# Snippet_LM1117MP-5_0.net
KiCad netlist of a schematic drawn in Altium Designer
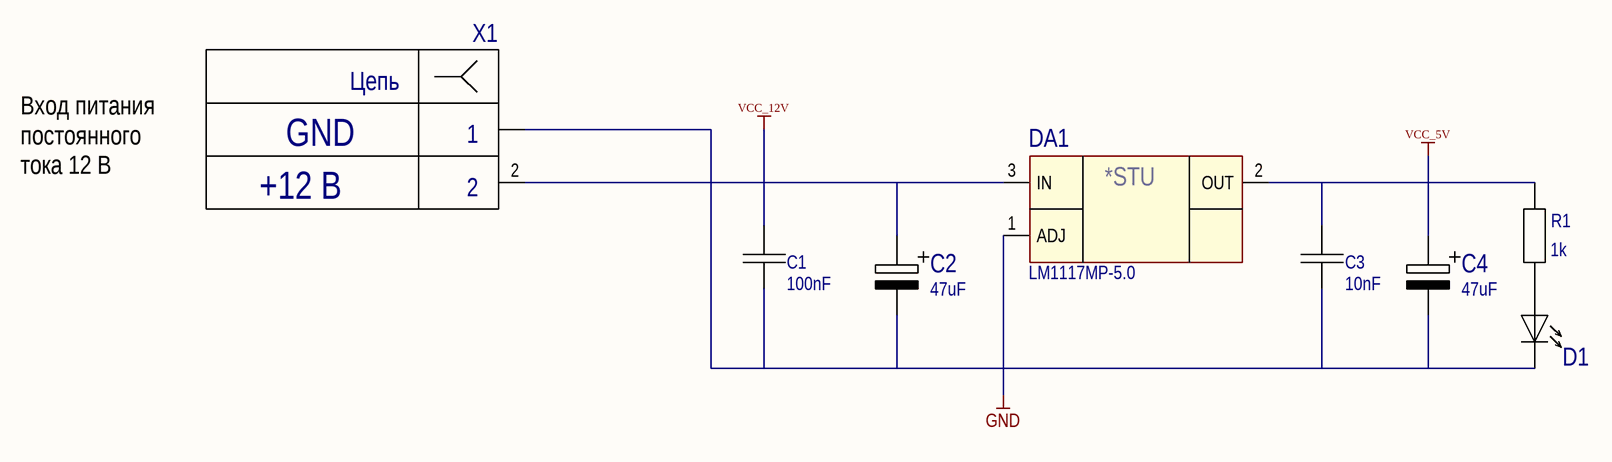
[diagram p0: Snippet_LM1117MP-5.0.SchDoc]

(export (version "E")
  (design (tool "Eeschema 10.0.6"))
  (components
    (comp (ref "C1")
      (value "100nF")
      (footprint "Capacitor_0805")
      (libsource (lib "Библиотека элементов") (part "Capacitor_0805"))
    )
    (comp (ref "C2")
      (value "47uF")
      (footprint "Capacitor_Electrolit_6.3x11")
      (libsource (lib "Библиотека элементов") (part "Capacitor+_6.3x11"))
    )
    (comp (ref "C3")
      (value "10nF")
      (footprint "Capacitor_0805")
      (libsource (lib "Библиотека элементов") (part "Capacitor_0805"))
    )
    (comp (ref "C4")
      (value "47uF")
      (footprint "CAPACITOR+_22uFx25V")
      (libsource (lib "Библиотека элементов") (part "Capacitor+_22uFx25V"))
    )
    (comp (ref "D1")
      (value "LED_2.54mm_R")
      (footprint "LED_2.54mm_R")
      (libsource (lib "Библиотека элементов") (part "LED_2.54mm_R"))
    )
    (comp (ref "DA1")
      (value "LM1117MP-5.0")
      (footprint "NCP1117_SOT223")
      (libsource (lib "Библиотека элементов") (part "LM1117MP-5.0"))
    )
    (comp (ref "R1")
      (value "1k")
      (footprint "RESISTOR_SMD0805")
      (libsource (lib "Библиотека элементов") (part "Resistor_0805"))
    )
    (comp (ref "X1")
      (value "Connector_DG350-3.5-02P-14")
      (footprint "CONNECTOR_DG350-3.5-02P-14")
      (libsource (lib "Библиотека элементов") (part "Connector_DG350-3.5-02P-14"))
    )
  )
  (nets
    (net (code "1") (name "GND") (class "Default")
      (node (ref "C1") (pin "2") (pinfunction "2_2") (pintype "passive"))
      (node (ref "C2") (pin "2") (pinfunction "2_2") (pintype "passive"))
      (node (ref "C3") (pin "2") (pinfunction "2_2") (pintype "passive"))
      (node (ref "C4") (pin "2") (pinfunction "2_2") (pintype "passive"))
      (node (ref "D1") (pin "1") (pinfunction "1_1") (pintype "passive"))
      (node (ref "DA1") (pin "1") (pinfunction "ADJ_1") (pintype "passive"))
      (node (ref "X1") (pin "1") (pinfunction "1_1") (pintype "passive"))
    )
    (net (code "2") (name "Net-(D1-Pad2)") (class "Default")
      (node (ref "D1") (pin "2") (pinfunction "2_2") (pintype "passive"))
      (node (ref "R1") (pin "1") (pinfunction "1_1") (pintype "passive"))
    )
    (net (code "3") (name "VCC_5V") (class "Default")
      (node (ref "C3") (pin "1") (pinfunction "1_1") (pintype "passive"))
      (node (ref "C4") (pin "1") (pinfunction "1_1") (pintype "passive"))
      (node (ref "DA1") (pin "2") (pinfunction "OUT_2") (pintype "power_in"))
      (node (ref "R1") (pin "2") (pinfunction "2_2") (pintype "passive"))
    )
    (net (code "4") (name "VCC_12V") (class "Default")
      (node (ref "C1") (pin "1") (pinfunction "1_1") (pintype "passive"))
      (node (ref "C2") (pin "1") (pinfunction "1_1") (pintype "passive"))
      (node (ref "DA1") (pin "3") (pinfunction "IN_3") (pintype "power_in"))
      (node (ref "X1") (pin "2") (pinfunction "2_2") (pintype "passive"))
    )
  )
)
